# EggDuino77.net
KiCad netlist of a schematic drawn in EAGLE
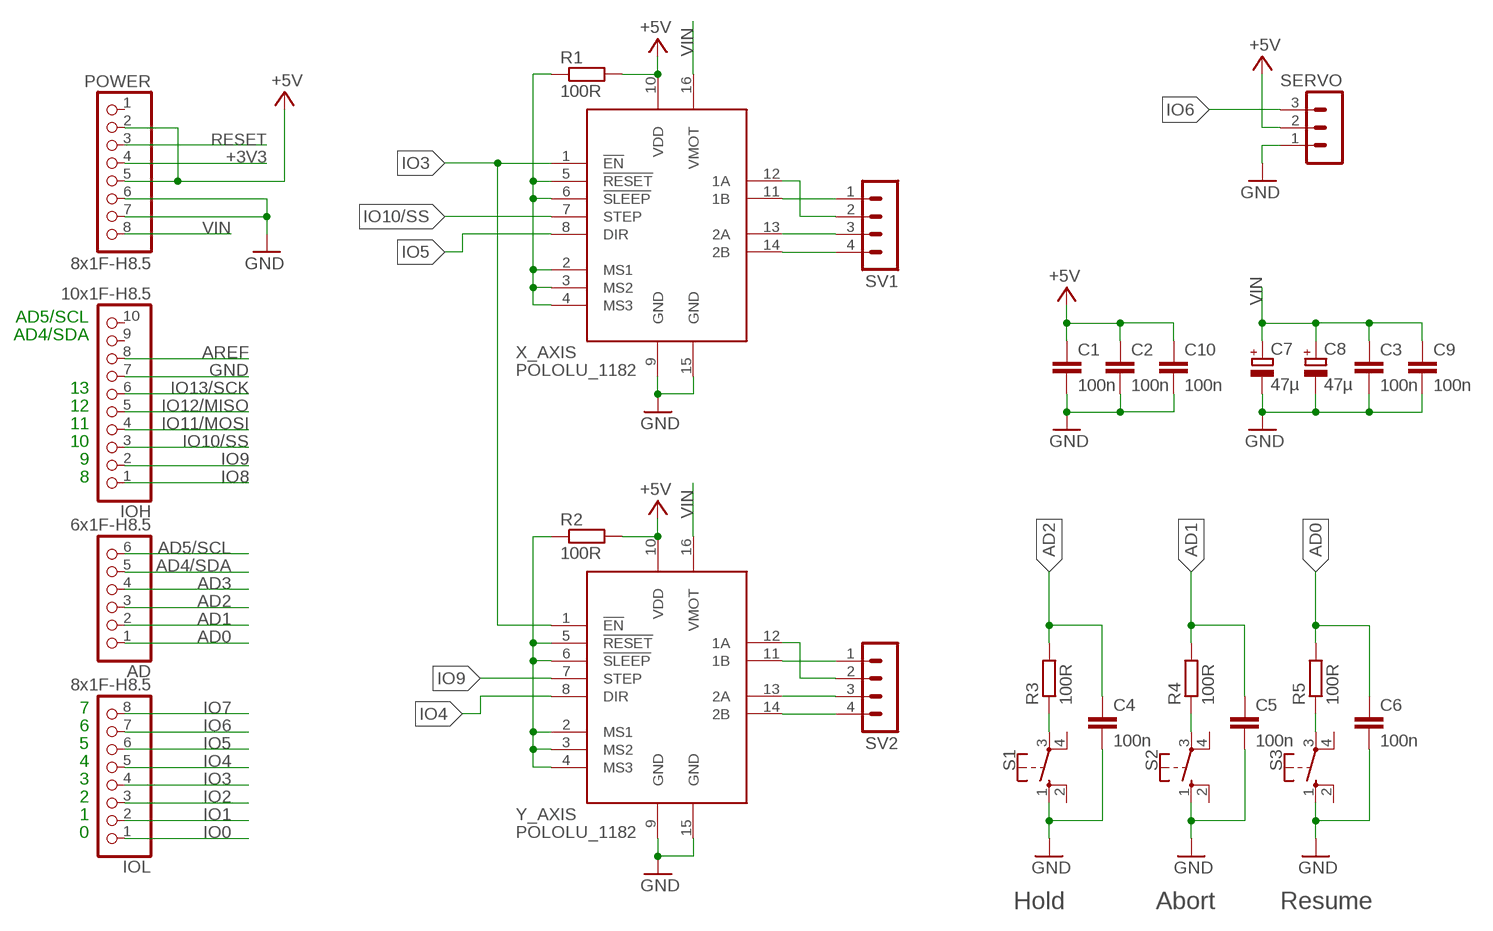
[diagram p0: schematic, sheet 1]

(export (version "E")
  (design (tool "Eeschema 10.0.6"))
  (components
    (comp (ref "AD")
      (value "6x1F-H8.5")
      (footprint "eagle-import:1X06")
      (libsource (lib "eagle-import") (part "PINHD-1X6"))
    )
    (comp (ref "C1")
      (value "100n")
      (footprint "eagle-import:C0805")
      (libsource (lib "eagle-import") (part "C-EUC0805"))
    )
    (comp (ref "C2")
      (value "100n")
      (footprint "eagle-import:C0805")
      (libsource (lib "eagle-import") (part "C-EUC0805"))
    )
    (comp (ref "C3")
      (value "100n")
      (footprint "eagle-import:C0805")
      (libsource (lib "eagle-import") (part "C-EUC0805"))
    )
    (comp (ref "C4")
      (value "100n")
      (footprint "eagle-import:C0805")
      (libsource (lib "eagle-import") (part "C-EUC0805"))
    )
    (comp (ref "C5")
      (value "100n")
      (footprint "eagle-import:C0805")
      (libsource (lib "eagle-import") (part "C-EUC0805"))
    )
    (comp (ref "C6")
      (value "100n")
      (footprint "eagle-import:C0805")
      (libsource (lib "eagle-import") (part "C-EUC0805"))
    )
    (comp (ref "C7")
      (value "47µ")
      (footprint "eagle-import:E2,5-6E")
      (libsource (lib "eagle-import") (part "CPOL-EUE2,5-6E"))
    )
    (comp (ref "C8")
      (value "47µ")
      (footprint "eagle-import:E2,5-6E")
      (libsource (lib "eagle-import") (part "CPOL-EUE2,5-6E"))
    )
    (comp (ref "C9")
      (value "100n")
      (footprint "eagle-import:C0805")
      (libsource (lib "eagle-import") (part "C-EUC0805"))
    )
    (comp (ref "C10")
      (value "100n")
      (footprint "eagle-import:C0805")
      (libsource (lib "eagle-import") (part "C-EUC0805"))
    )
    (comp (ref "IOH")
      (value "10x1F-H8.5")
      (footprint "eagle-import:1X10")
      (libsource (lib "eagle-import") (part "PINHD-1X10_ARD"))
    )
    (comp (ref "IOL")
      (value "8x1F-H8.5")
      (footprint "eagle-import:1X08")
      (libsource (lib "eagle-import") (part "PINHD-1X8"))
    )
    (comp (ref "POWER")
      (value "8x1F-H8.5")
      (footprint "eagle-import:1X08")
      (libsource (lib "eagle-import") (part "PINHD-1X8"))
    )
    (comp (ref "R1")
      (value "100R")
      (footprint "eagle-import:R0805")
      (libsource (lib "eagle-import") (part "R-EU_R0805"))
    )
    (comp (ref "R2")
      (value "100R")
      (footprint "eagle-import:R0805")
      (libsource (lib "eagle-import") (part "R-EU_R0805"))
    )
    (comp (ref "R3")
      (value "100R")
      (footprint "eagle-import:R0805")
      (libsource (lib "eagle-import") (part "R-EU_R0805"))
    )
    (comp (ref "R4")
      (value "100R")
      (footprint "eagle-import:R0805")
      (libsource (lib "eagle-import") (part "R-EU_R0805"))
    )
    (comp (ref "R5")
      (value "100R")
      (footprint "eagle-import:R0805")
      (libsource (lib "eagle-import") (part "R-EU_R0805"))
    )
    (comp (ref "S1")
      (value "10-XX")
      (footprint "eagle-import:B3F-10XX")
      (libsource (lib "eagle-import") (part "10-XX"))
    )
    (comp (ref "S2")
      (value "10-XX")
      (footprint "eagle-import:B3F-10XX")
      (libsource (lib "eagle-import") (part "10-XX"))
    )
    (comp (ref "S3")
      (value "10-XX")
      (footprint "eagle-import:B3F-10XX")
      (libsource (lib "eagle-import") (part "10-XX"))
    )
    (comp (ref "SERVO")
      (value "MA03-1")
      (footprint "eagle-import:MA03-1")
      (libsource (lib "eagle-import") (part "MA03-1"))
    )
    (comp (ref "SV1")
      (value "MA04-1")
      (footprint "eagle-import:MA04-1")
      (libsource (lib "eagle-import") (part "MA04-1"))
    )
    (comp (ref "SV2")
      (value "MA04-1")
      (footprint "eagle-import:MA04-1")
      (libsource (lib "eagle-import") (part "MA04-1"))
    )
    (comp (ref "X_AXIS")
      (value "POLOLU_1182")
      (footprint "eagle-import:DIL16_WIDE")
      (libsource (lib "eagle-import") (part "POLOLU_1182"))
    )
    (comp (ref "Y_AXIS")
      (value "POLOLU_1182")
      (footprint "eagle-import:DIL16_WIDE")
      (libsource (lib "eagle-import") (part "POLOLU_1182"))
    )
  )
  (nets
    (net (code "1") (name "+5V") (class "Default")
      (node (ref "C1") (pin "1") (pinfunction "1_1") (pintype "passive"))
      (node (ref "C10") (pin "1") (pinfunction "1_1") (pintype "passive"))
      (node (ref "C2") (pin "1") (pinfunction "1_1") (pintype "passive"))
      (node (ref "POWER") (pin "2") (pinfunction "2_2") (pintype "passive"))
      (node (ref "POWER") (pin "5") (pinfunction "5_5") (pintype "passive"))
      (node (ref "R1") (pin "2") (pinfunction "2_2") (pintype "passive"))
      (node (ref "R2") (pin "2") (pinfunction "2_2") (pintype "passive"))
      (node (ref "SERVO") (pin "2") (pinfunction "2_2") (pintype "passive"))
      (node (ref "X_AXIS") (pin "10") (pinfunction "VDD_10") (pintype "power_in"))
      (node (ref "Y_AXIS") (pin "10") (pinfunction "VDD_10") (pintype "power_in"))
    )
    (net (code "2") (name "/+3V3") (class "Default")
      (node (ref "POWER") (pin "4") (pinfunction "4_4") (pintype "passive"))
    )
    (net (code "3") (name "/AD3") (class "Default")
      (node (ref "AD") (pin "4") (pinfunction "4_4") (pintype "passive"))
    )
    (net (code "4") (name "/AD4{slash}SDA") (class "Default")
      (node (ref "AD") (pin "5") (pinfunction "5_5") (pintype "passive"))
    )
    (net (code "5") (name "/AD5{slash}SCL") (class "Default")
      (node (ref "AD") (pin "6") (pinfunction "6_6") (pintype "passive"))
    )
    (net (code "6") (name "/AREF") (class "Default")
      (node (ref "IOH") (pin "8") (pinfunction "8_8") (pintype "passive"))
    )
    (net (code "7") (name "/IO0") (class "Default")
      (node (ref "IOL") (pin "1") (pinfunction "1_1") (pintype "passive"))
    )
    (net (code "8") (name "/IO1") (class "Default")
      (node (ref "IOL") (pin "2") (pinfunction "2_2") (pintype "passive"))
    )
    (net (code "9") (name "/IO2") (class "Default")
      (node (ref "IOL") (pin "3") (pinfunction "3_3") (pintype "passive"))
    )
    (net (code "10") (name "/IO7") (class "Default")
      (node (ref "IOL") (pin "8") (pinfunction "8_8") (pintype "passive"))
    )
    (net (code "11") (name "/IO8") (class "Default")
      (node (ref "IOH") (pin "1") (pinfunction "1_1") (pintype "passive"))
    )
    (net (code "12") (name "/IO11{slash}MOSI") (class "Default")
      (node (ref "IOH") (pin "4") (pinfunction "4_4") (pintype "passive"))
    )
    (net (code "13") (name "/IO12{slash}MISO") (class "Default")
      (node (ref "IOH") (pin "5") (pinfunction "5_5") (pintype "passive"))
    )
    (net (code "14") (name "/IO13{slash}SCK") (class "Default")
      (node (ref "IOH") (pin "6") (pinfunction "6_6") (pintype "passive"))
    )
    (net (code "15") (name "/RESET") (class "Default")
      (node (ref "POWER") (pin "3") (pinfunction "3_3") (pintype "passive"))
    )
    (net (code "16") (name "/VIN") (class "Default")
      (node (ref "C3") (pin "1") (pinfunction "1_1") (pintype "passive"))
      (node (ref "C7") (pin "+") (pinfunction "+_+") (pintype "passive"))
      (node (ref "C8") (pin "+") (pinfunction "+_+") (pintype "passive"))
      (node (ref "C9") (pin "1") (pinfunction "1_1") (pintype "passive"))
      (node (ref "POWER") (pin "8") (pinfunction "8_8") (pintype "passive"))
      (node (ref "X_AXIS") (pin "16") (pinfunction "VMOT_16") (pintype "power_in"))
      (node (ref "Y_AXIS") (pin "16") (pinfunction "VMOT_16") (pintype "power_in"))
    )
    (net (code "17") (name "AD0") (class "Default")
      (node (ref "AD") (pin "1") (pinfunction "1_1") (pintype "passive"))
      (node (ref "C6") (pin "1") (pinfunction "1_1") (pintype "passive"))
      (node (ref "R5") (pin "2") (pinfunction "2_2") (pintype "passive"))
    )
    (net (code "18") (name "AD1") (class "Default")
      (node (ref "AD") (pin "2") (pinfunction "2_2") (pintype "passive"))
      (node (ref "C5") (pin "1") (pinfunction "1_1") (pintype "passive"))
      (node (ref "R4") (pin "2") (pinfunction "2_2") (pintype "passive"))
    )
    (net (code "19") (name "AD2") (class "Default")
      (node (ref "AD") (pin "3") (pinfunction "3_3") (pintype "passive"))
      (node (ref "C4") (pin "1") (pinfunction "1_1") (pintype "passive"))
      (node (ref "R3") (pin "2") (pinfunction "2_2") (pintype "passive"))
    )
    (net (code "20") (name "GND") (class "Default")
      (node (ref "C1") (pin "2") (pinfunction "2_2") (pintype "passive"))
      (node (ref "C10") (pin "2") (pinfunction "2_2") (pintype "passive"))
      (node (ref "C2") (pin "2") (pinfunction "2_2") (pintype "passive"))
      (node (ref "C3") (pin "2") (pinfunction "2_2") (pintype "passive"))
      (node (ref "C4") (pin "2") (pinfunction "2_2") (pintype "passive"))
      (node (ref "C5") (pin "2") (pinfunction "2_2") (pintype "passive"))
      (node (ref "C6") (pin "2") (pinfunction "2_2") (pintype "passive"))
      (node (ref "C7") (pin "-") (pinfunction "-_-") (pintype "passive"))
      (node (ref "C8") (pin "-") (pinfunction "-_-") (pintype "passive"))
      (node (ref "C9") (pin "2") (pinfunction "2_2") (pintype "passive"))
      (node (ref "IOH") (pin "7") (pinfunction "7_7") (pintype "passive"))
      (node (ref "POWER") (pin "6") (pinfunction "6_6") (pintype "passive"))
      (node (ref "POWER") (pin "7") (pinfunction "7_7") (pintype "passive"))
      (node (ref "S1") (pin "1") (pinfunction "S_1") (pintype "passive"))
      (node (ref "S2") (pin "1") (pinfunction "S_1") (pintype "passive"))
      (node (ref "S3") (pin "1") (pinfunction "S_1") (pintype "passive"))
      (node (ref "SERVO") (pin "1") (pinfunction "1_1") (pintype "passive"))
      (node (ref "X_AXIS") (pin "15") (pinfunction "GND_15") (pintype "power_in"))
      (node (ref "X_AXIS") (pin "9") (pinfunction "GND_9") (pintype "power_in"))
      (node (ref "Y_AXIS") (pin "15") (pinfunction "GND_15") (pintype "power_in"))
      (node (ref "Y_AXIS") (pin "9") (pinfunction "GND_9") (pintype "power_in"))
    )
    (net (code "21") (name "IO3") (class "Default")
      (node (ref "IOL") (pin "4") (pinfunction "4_4") (pintype "passive"))
      (node (ref "X_AXIS") (pin "1") (pinfunction "~{EN}_1") (pintype "input"))
      (node (ref "Y_AXIS") (pin "1") (pinfunction "~{EN}_1") (pintype "input"))
    )
    (net (code "22") (name "IO4") (class "Default")
      (node (ref "IOL") (pin "5") (pinfunction "5_5") (pintype "passive"))
      (node (ref "Y_AXIS") (pin "8") (pinfunction "DIR_8") (pintype "input"))
    )
    (net (code "23") (name "IO5") (class "Default")
      (node (ref "IOL") (pin "6") (pinfunction "6_6") (pintype "passive"))
      (node (ref "X_AXIS") (pin "8") (pinfunction "DIR_8") (pintype "input"))
    )
    (net (code "24") (name "IO6") (class "Default")
      (node (ref "IOL") (pin "7") (pinfunction "7_7") (pintype "passive"))
      (node (ref "SERVO") (pin "3") (pinfunction "3_3") (pintype "passive"))
    )
    (net (code "25") (name "IO9") (class "Default")
      (node (ref "IOH") (pin "2") (pinfunction "2_2") (pintype "passive"))
      (node (ref "Y_AXIS") (pin "7") (pinfunction "STEP_7") (pintype "input"))
    )
    (net (code "26") (name "IO10{slash}SS") (class "Default")
      (node (ref "IOH") (pin "3") (pinfunction "3_3") (pintype "passive"))
      (node (ref "X_AXIS") (pin "7") (pinfunction "STEP_7") (pintype "input"))
    )
    (net (code "27") (name "Net-(S1-P)") (class "Default")
      (node (ref "R3") (pin "1") (pinfunction "1_1") (pintype "passive"))
      (node (ref "S1") (pin "3") (pinfunction "P_3") (pintype "passive"))
    )
    (net (code "28") (name "Net-(S2-P)") (class "Default")
      (node (ref "R4") (pin "1") (pinfunction "1_1") (pintype "passive"))
      (node (ref "S2") (pin "3") (pinfunction "P_3") (pintype "passive"))
    )
    (net (code "29") (name "Net-(S3-P)") (class "Default")
      (node (ref "R5") (pin "1") (pinfunction "1_1") (pintype "passive"))
      (node (ref "S3") (pin "3") (pinfunction "P_3") (pintype "passive"))
    )
    (net (code "30") (name "Net-(X_AXIS-1A)") (class "Default")
      (node (ref "SV1") (pin "2") (pinfunction "2_2") (pintype "passive"))
      (node (ref "X_AXIS") (pin "12") (pinfunction "1A_12") (pintype "output"))
    )
    (net (code "31") (name "Net-(X_AXIS-1B)") (class "Default")
      (node (ref "SV1") (pin "1") (pinfunction "1_1") (pintype "passive"))
      (node (ref "X_AXIS") (pin "11") (pinfunction "1B_11") (pintype "output"))
    )
    (net (code "32") (name "Net-(X_AXIS-2A)") (class "Default")
      (node (ref "SV1") (pin "3") (pinfunction "3_3") (pintype "passive"))
      (node (ref "X_AXIS") (pin "13") (pinfunction "2A_13") (pintype "output"))
    )
    (net (code "33") (name "Net-(X_AXIS-2B)") (class "Default")
      (node (ref "SV1") (pin "4") (pinfunction "4_4") (pintype "passive"))
      (node (ref "X_AXIS") (pin "14") (pinfunction "2B_14") (pintype "output"))
    )
    (net (code "34") (name "Net-(X_AXIS-MS1)") (class "Default")
      (node (ref "R1") (pin "1") (pinfunction "1_1") (pintype "passive"))
      (node (ref "X_AXIS") (pin "2") (pinfunction "MS1_2") (pintype "input"))
      (node (ref "X_AXIS") (pin "3") (pinfunction "MS2_3") (pintype "input"))
      (node (ref "X_AXIS") (pin "4") (pinfunction "MS3_4") (pintype "input"))
      (node (ref "X_AXIS") (pin "5") (pinfunction "~{RESET}_5") (pintype "input"))
      (node (ref "X_AXIS") (pin "6") (pinfunction "~{SLEEP}_6") (pintype "input"))
    )
    (net (code "35") (name "Net-(Y_AXIS-1A)") (class "Default")
      (node (ref "SV2") (pin "2") (pinfunction "2_2") (pintype "passive"))
      (node (ref "Y_AXIS") (pin "12") (pinfunction "1A_12") (pintype "output"))
    )
    (net (code "36") (name "Net-(Y_AXIS-1B)") (class "Default")
      (node (ref "SV2") (pin "1") (pinfunction "1_1") (pintype "passive"))
      (node (ref "Y_AXIS") (pin "11") (pinfunction "1B_11") (pintype "output"))
    )
    (net (code "37") (name "Net-(Y_AXIS-2A)") (class "Default")
      (node (ref "SV2") (pin "3") (pinfunction "3_3") (pintype "passive"))
      (node (ref "Y_AXIS") (pin "13") (pinfunction "2A_13") (pintype "output"))
    )
    (net (code "38") (name "Net-(Y_AXIS-2B)") (class "Default")
      (node (ref "SV2") (pin "4") (pinfunction "4_4") (pintype "passive"))
      (node (ref "Y_AXIS") (pin "14") (pinfunction "2B_14") (pintype "output"))
    )
    (net (code "39") (name "Net-(Y_AXIS-MS1)") (class "Default")
      (node (ref "R2") (pin "1") (pinfunction "1_1") (pintype "passive"))
      (node (ref "Y_AXIS") (pin "2") (pinfunction "MS1_2") (pintype "input"))
      (node (ref "Y_AXIS") (pin "3") (pinfunction "MS2_3") (pintype "input"))
      (node (ref "Y_AXIS") (pin "4") (pinfunction "MS3_4") (pintype "input"))
      (node (ref "Y_AXIS") (pin "5") (pinfunction "~{RESET}_5") (pintype "input"))
      (node (ref "Y_AXIS") (pin "6") (pinfunction "~{SLEEP}_6") (pintype "input"))
    )
    (net (code "40") (name "unconnected-(IOH-Pad9)") (class "Default")
      (node (ref "IOH") (pin "9") (pinfunction "9_9") (pintype "passive"))
    )
    (net (code "41") (name "unconnected-(IOH-Pad10)") (class "Default")
      (node (ref "IOH") (pin "10") (pinfunction "10_10") (pintype "passive"))
    )
    (net (code "42") (name "unconnected-(POWER-Pad1)") (class "Default")
      (node (ref "POWER") (pin "1") (pinfunction "1_1") (pintype "passive"))
    )
    (net (code "43") (name "unconnected-(S1-P1-Pad4)") (class "Default")
      (node (ref "S1") (pin "4") (pinfunction "P1_4") (pintype "passive"))
    )
    (net (code "44") (name "unconnected-(S1-S1-Pad2)") (class "Default")
      (node (ref "S1") (pin "2") (pinfunction "S1_2") (pintype "passive"))
    )
    (net (code "45") (name "unconnected-(S2-P1-Pad4)") (class "Default")
      (node (ref "S2") (pin "4") (pinfunction "P1_4") (pintype "passive"))
    )
    (net (code "46") (name "unconnected-(S2-S1-Pad2)") (class "Default")
      (node (ref "S2") (pin "2") (pinfunction "S1_2") (pintype "passive"))
    )
    (net (code "47") (name "unconnected-(S3-P1-Pad4)") (class "Default")
      (node (ref "S3") (pin "4") (pinfunction "P1_4") (pintype "passive"))
    )
    (net (code "48") (name "unconnected-(S3-S1-Pad2)") (class "Default")
      (node (ref "S3") (pin "2") (pinfunction "S1_2") (pintype "passive"))
    )
  )
)
